# Out.net
KiCad netlist of a schematic drawn in Altium Designer
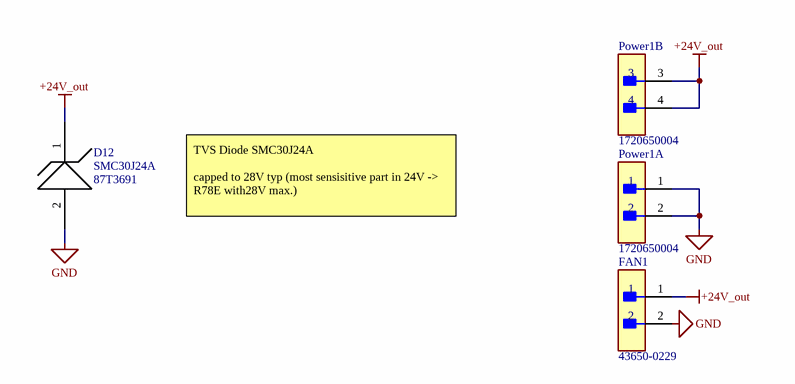
[diagram p0: Out.SchDoc]

(export (version "E")
  (design (tool "Eeschema 10.0.6"))
  (components
    (comp (ref "D12")
      (value "SMC30J24A")
      (footprint "JEDEC DO-214AB")
      (description "3000 W TVS in SMC package")
      (fields
        (field (name "MANUFACTURER") "STMicroelectronics")
        (field (name "SUPPLIER PART NUMBER 1") "87T3691")
      )
      (libsource (lib "Integrated_LibraryLukas") (part "SMC30J24A"))
    )
    (comp (ref "FAN1")
      (value "43650-0229")
      (footprint "FP-43650-0229-MFG")
      (description "CONN HEADER VERT 2POS 3MM")
      (fields
        (field (name "OCTOPART") "https://octopart.com/43650-0229-molex-7652326")
        (field (name "MANUFACTURER") "Molex")
      )
      (libsource (lib "Altium Content Vault") (part "3bc925449376181038e59eaffc5286c"))
    )
    (comp (ref "Power1")
      (value "1720650004")
      (footprint "FP-1720650004-MFG")
      (description "CONN HEADER VERT 4POS 5.7MM")
      (fields
        (field (name "MANUFACTURER") "Molex")
        (field (name "OCTOPART") "https://octopart.com/172065-0004-molex-34473112")
      )
      (libsource (lib "Altium Content Vault") (part "ac72c5313ea981db199dbd0e8237b04"))
    )
  )
  (nets
    (net (code "1") (name "+24V_out") (class "Default")
      (node (ref "D12") (pin "1") (pintype "passive"))
      (node (ref "FAN1") (pin "1") (pinfunction "1_1") (pintype "passive"))
      (node (ref "Power1") (pin "3") (pinfunction "3_3") (pintype "passive"))
      (node (ref "Power1") (pin "4") (pinfunction "4_4") (pintype "passive"))
    )
    (net (code "2") (name "GND") (class "Default")
      (node (ref "D12") (pin "2") (pintype "passive"))
      (node (ref "FAN1") (pin "2") (pinfunction "2_2") (pintype "passive"))
      (node (ref "Power1") (pin "1") (pinfunction "1_1") (pintype "passive"))
      (node (ref "Power1") (pin "2") (pinfunction "2_2") (pintype "passive"))
    )
  )
)
